# SD_UART_Sensor.net
KiCad netlist of a schematic drawn in Altium Designer
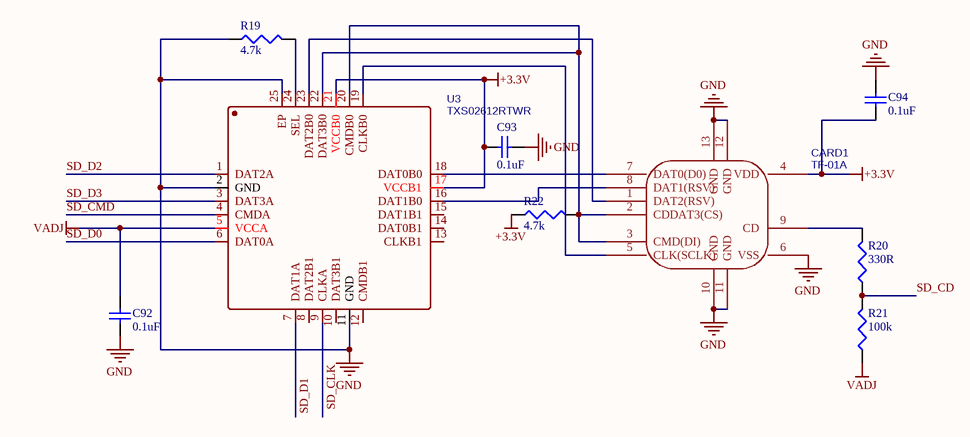
[diagram p0: SD&UART&Sensor.SchDoc]

(export (version "E")
  (design (tool "Eeschema 10.0.6"))
  (components
    (comp (ref "C92")
      (value "0.1uF")
      (footprint "0402")
      (description "Capacitor (Semiconductor SIM Model)")
      (fields (field (name "Comment") "Cap Semi") (field (name "PUBLISHER") "Altium Limited"))
      (libsource (lib "Miscellaneous Devices") (part "Cap Semi"))
    )
    (comp (ref "C93")
      (value "0.1uF")
      (footprint "0402")
      (description "Capacitor (Semiconductor SIM Model)")
      (fields (field (name "Comment") "Cap Semi") (field (name "PUBLISHER") "Altium Limited"))
      (libsource (lib "Miscellaneous Devices") (part "Cap Semi"))
    )
    (comp (ref "C94")
      (value "0.1uF")
      (footprint "0402")
      (description "Capacitor (Semiconductor SIM Model)")
      (fields (field (name "Comment") "Cap Semi") (field (name "PUBLISHER") "Altium Limited"))
      (libsource (lib "Miscellaneous Devices") (part "Cap Semi"))
    )
    (comp (ref "CARD1")
      (value "TF-01A")
      (footprint "MICRO_SD")
      (fields (field (name "BOM_SUPPLIER PART") "C91145"))
      (libsource (lib "Schlib1") (part "TF-01A"))
    )
    (comp (ref "R19")
      (value "4.7k")
      (footprint "J1-0603")
      (description "Resistor")
      (fields (field (name "Comment") "Res3") (field (name "PUBLISHER") "Altium Limited"))
      (libsource (lib "Miscellaneous Devices") (part "Res3"))
    )
    (comp (ref "R20")
      (value "330R")
      (footprint "J1-0603")
      (description "Resistor")
      (fields (field (name "Comment") "Res3") (field (name "PUBLISHER") "Altium Limited"))
      (libsource (lib "Miscellaneous Devices") (part "Res3"))
    )
    (comp (ref "R21")
      (value "100k")
      (footprint "J1-0603")
      (description "Resistor")
      (fields (field (name "Comment") "Res3") (field (name "PUBLISHER") "Altium Limited"))
      (libsource (lib "Miscellaneous Devices") (part "Res3"))
    )
    (comp (ref "R22")
      (value "4.7k")
      (footprint "J1-0603")
      (description "Resistor")
      (fields (field (name "Comment") "Res3") (field (name "PUBLISHER") "Altium Limited"))
      (libsource (lib "Miscellaneous Devices") (part "Res3"))
    )
    (comp (ref "U3")
      (value "TXS02612RTWR")
      (footprint "QFN24_RTW")
      (fields (field (name "BOM_SUPPLIER PART") "C140276") (field (name "CONTRIBUTOR") "LCSC"))
      (libsource (lib "Schlib1") (part "TXS02612RTWR"))
    )
  )
  (nets
    (net (code "1") (name "+3.3V") (class "Default")
      (node (ref "C93") (pin "2") (pinfunction "2_2") (pintype "passive"))
      (node (ref "C94") (pin "1") (pinfunction "1_1") (pintype "passive"))
      (node (ref "CARD1") (pin "4") (pinfunction "VDD_4") (pintype "passive"))
      (node (ref "R22") (pin "1") (pinfunction "1_1") (pintype "passive"))
      (node (ref "U3") (pin "17") (pinfunction "VCCB1_17") (pintype "passive"))
      (node (ref "U3") (pin "21") (pinfunction "VCCB0_21") (pintype "passive"))
    )
    (net (code "2") (name "/SD_CD") (class "Default")
      (node (ref "R20") (pin "1") (pinfunction "1_1") (pintype "passive"))
      (node (ref "R21") (pin "2") (pinfunction "2_2") (pintype "passive"))
    )
    (net (code "3") (name "/SD_CLK") (class "Default")
      (node (ref "U3") (pin "9") (pinfunction "CLKA_9") (pintype "passive"))
    )
    (net (code "4") (name "/SD_CMD") (class "Default")
      (node (ref "U3") (pin "4") (pinfunction "CMDA_4") (pintype "passive"))
    )
    (net (code "5") (name "/SD_D0") (class "Default")
      (node (ref "U3") (pin "6") (pinfunction "DAT0A_6") (pintype "passive"))
    )
    (net (code "6") (name "/SD_D1") (class "Default")
      (node (ref "U3") (pin "7") (pinfunction "DAT1A_7") (pintype "passive"))
    )
    (net (code "7") (name "/SD_D2") (class "Default")
      (node (ref "U3") (pin "1") (pinfunction "DAT2A_1") (pintype "passive"))
    )
    (net (code "8") (name "/SD_D3") (class "Default")
      (node (ref "U3") (pin "3") (pinfunction "DAT3A_3") (pintype "passive"))
    )
    (net (code "9") (name "GND") (class "Default")
      (node (ref "C92") (pin "1") (pinfunction "1_1") (pintype "passive"))
      (node (ref "C93") (pin "1") (pinfunction "1_1") (pintype "passive"))
      (node (ref "C94") (pin "2") (pinfunction "2_2") (pintype "passive"))
      (node (ref "CARD1") (pin "10") (pinfunction "GND_10") (pintype "passive"))
      (node (ref "CARD1") (pin "11") (pinfunction "GND_11") (pintype "passive"))
      (node (ref "CARD1") (pin "12") (pinfunction "GND_12") (pintype "passive"))
      (node (ref "CARD1") (pin "13") (pinfunction "GND_13") (pintype "passive"))
      (node (ref "CARD1") (pin "6") (pinfunction "VSS_6") (pintype "passive"))
      (node (ref "R19") (pin "1") (pinfunction "1_1") (pintype "passive"))
      (node (ref "U3") (pin "11") (pinfunction "GND_11") (pintype "passive"))
      (node (ref "U3") (pin "2") (pinfunction "GND_2") (pintype "passive"))
      (node (ref "U3") (pin "25") (pinfunction "EP_25") (pintype "passive"))
    )
    (net (code "10") (name "Net-(CARD1-CD)") (class "Default")
      (node (ref "CARD1") (pin "9") (pinfunction "CD_9") (pintype "passive"))
      (node (ref "R20") (pin "2") (pinfunction "2_2") (pintype "passive"))
    )
    (net (code "11") (name "Net-(CARD1-CDDAT3(CS))") (class "Default")
      (node (ref "CARD1") (pin "2") (pinfunction "CDDAT3(CS)_2") (pintype "passive"))
      (node (ref "CARD1") (pin "3") (pinfunction "CMD(DI)_3") (pintype "passive"))
      (node (ref "R22") (pin "2") (pinfunction "2_2") (pintype "passive"))
      (node (ref "U3") (pin "20") (pinfunction "CMDB0_20") (pintype "passive"))
      (node (ref "U3") (pin "22") (pinfunction "DAT3B0_22") (pintype "passive"))
    )
    (net (code "12") (name "Net-(CARD1-CLK(SCLK))") (class "Default")
      (node (ref "CARD1") (pin "5") (pinfunction "CLK(SCLK)_5") (pintype "passive"))
      (node (ref "U3") (pin "19") (pinfunction "CLKB0_19") (pintype "passive"))
    )
    (net (code "13") (name "Net-(CARD1-DAT0(D0))") (class "Default")
      (node (ref "CARD1") (pin "7") (pinfunction "DAT0(D0)_7") (pintype "passive"))
      (node (ref "U3") (pin "18") (pinfunction "DAT0B0_18") (pintype "passive"))
    )
    (net (code "14") (name "Net-(CARD1-DAT1(RSV))") (class "Default")
      (node (ref "CARD1") (pin "8") (pinfunction "DAT1(RSV)_8") (pintype "passive"))
      (node (ref "U3") (pin "16") (pinfunction "DAT1B0_16") (pintype "passive"))
    )
    (net (code "15") (name "Net-(CARD1-DAT2(RSV))") (class "Default")
      (node (ref "CARD1") (pin "1") (pinfunction "DAT2(RSV)_1") (pintype "passive"))
      (node (ref "U3") (pin "23") (pinfunction "DAT2B0_23") (pintype "passive"))
    )
    (net (code "16") (name "Net-(U3-SEL)") (class "Default")
      (node (ref "R19") (pin "2") (pinfunction "2_2") (pintype "passive"))
      (node (ref "U3") (pin "24") (pinfunction "SEL_24") (pintype "passive"))
    )
    (net (code "17") (name "VADJ") (class "Default")
      (node (ref "C92") (pin "2") (pinfunction "2_2") (pintype "passive"))
      (node (ref "R21") (pin "1") (pinfunction "1_1") (pintype "passive"))
      (node (ref "U3") (pin "5") (pinfunction "VCCA_5") (pintype "passive"))
    )
    (net (code "18") (name "unconnected-(U3-CLKB1-Pad13)") (class "Default")
      (node (ref "U3") (pin "13") (pinfunction "CLKB1_13") (pintype "passive"))
    )
    (net (code "19") (name "unconnected-(U3-CMDB1-Pad12)") (class "Default")
      (node (ref "U3") (pin "12") (pinfunction "CMDB1_12") (pintype "passive"))
    )
    (net (code "20") (name "unconnected-(U3-DAT0B1-Pad14)") (class "Default")
      (node (ref "U3") (pin "14") (pinfunction "DAT0B1_14") (pintype "passive"))
    )
    (net (code "21") (name "unconnected-(U3-DAT1B1-Pad15)") (class "Default")
      (node (ref "U3") (pin "15") (pinfunction "DAT1B1_15") (pintype "passive"))
    )
    (net (code "22") (name "unconnected-(U3-DAT2B1-Pad8)") (class "Default")
      (node (ref "U3") (pin "8") (pinfunction "DAT2B1_8") (pintype "passive"))
    )
    (net (code "23") (name "unconnected-(U3-DAT3B1-Pad10)") (class "Default")
      (node (ref "U3") (pin "10") (pinfunction "DAT3B1_10") (pintype "passive"))
    )
  )
)
